# HELLO1.net
KiCad netlist of a schematic drawn in EAGLE
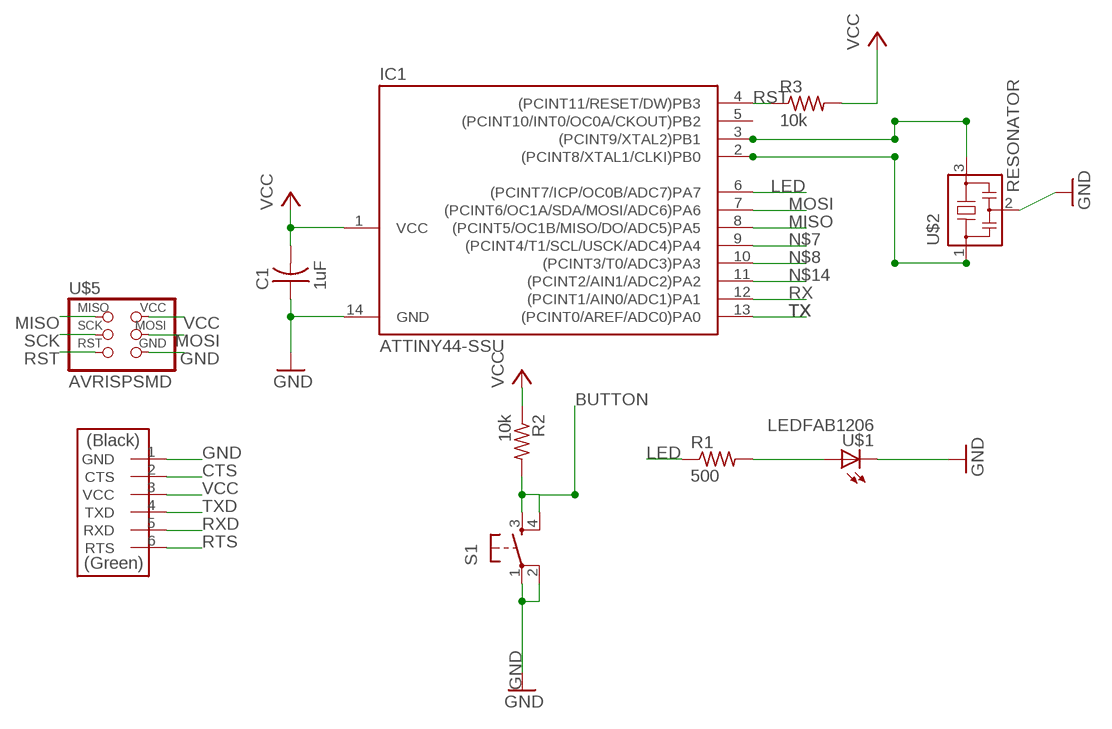
[diagram p0: schematic, sheet 1]

(export (version "E")
  (design (tool "Eeschema 10.0.6"))
  (components
    (comp (ref "C1")
      (value "1uF")
      (footprint "eagle-import:C1206FAB")
      (libsource (lib "eagle-import") (part "CAP-US1206FAB"))
    )
    (comp (ref "IC1")
      (value "ATTINY44-SSU")
      (footprint "eagle-import:SOIC14")
      (libsource (lib "eagle-import") (part "ATTINY44-SSU"))
    )
    (comp (ref "R1")
      (value "500")
      (footprint "eagle-import:R1206FAB")
      (libsource (lib "eagle-import") (part "RES-US1206FAB"))
    )
    (comp (ref "R2")
      (value "10k")
      (footprint "eagle-import:R1206FAB")
      (libsource (lib "eagle-import") (part "RES-US1206FAB"))
    )
    (comp (ref "R3")
      (value "10k")
      (footprint "eagle-import:R1206FAB")
      (libsource (lib "eagle-import") (part "RES-US1206FAB"))
    )
    (comp (ref "S1")
      (value "6MM_SWITCH6MM_SWITCH")
      (footprint "eagle-import:6MM_SWITCH")
      (libsource (lib "eagle-import") (part "6MM_SWITCH6MM_SWITCH"))
    )
    (comp (ref "U$1")
      (value "LEDFAB1206")
      (footprint "eagle-import:LED1206FAB")
      (libsource (lib "eagle-import") (part "LEDFAB1206"))
    )
    (comp (ref "U$2")
      (value "RESONATOR")
      (footprint "eagle-import:EFOBM")
      (libsource (lib "eagle-import") (part "RESONATOR"))
    )
    (comp (ref "U$4")
      (value "FTDI-SMD-HEADER")
      (footprint "eagle-import:1X06SMD")
      (libsource (lib "eagle-import") (part "FTDI-SMD-HEADER"))
    )
    (comp (ref "U$5")
      (value "AVRISPSMD")
      (footprint "eagle-import:2X03SMD")
      (libsource (lib "eagle-import") (part "AVRISPSMD"))
    )
  )
  (nets
    (net (code "1") (name "/BUTTON") (class "Default")
      (node (ref "R2") (pin "2") (pinfunction "2_2") (pintype "passive"))
      (node (ref "S1") (pin "3") (pinfunction "S_3") (pintype "passive"))
      (node (ref "S1") (pin "4") (pinfunction "S1_4") (pintype "passive"))
    )
    (net (code "2") (name "/CTS") (class "Default")
      (node (ref "U$4") (pin "2") (pinfunction "CTS_2") (pintype "bidirectional"))
    )
    (net (code "3") (name "/LED") (class "Default")
      (node (ref "IC1") (pin "6") (pinfunction "(PCINT7/ICP/OC0B/ADC7)PA7_6") (pintype "bidirectional"))
      (node (ref "R1") (pin "1") (pinfunction "1_1") (pintype "passive"))
    )
    (net (code "4") (name "/MISO") (class "Default")
      (node (ref "IC1") (pin "8") (pinfunction "(PCINT5/OC1B/MISO/DO/ADC5)PA5_8") (pintype "bidirectional"))
      (node (ref "U$5") (pin "1") (pinfunction "MISO_1") (pintype "passive"))
    )
    (net (code "5") (name "/MOSI") (class "Default")
      (node (ref "IC1") (pin "7") (pinfunction "(PCINT6/OC1A/SDA/MOSI/ADC6)PA6_7") (pintype "bidirectional"))
      (node (ref "U$5") (pin "4") (pinfunction "MOSI_4") (pintype "passive"))
    )
    (net (code "6") (name "/N$7") (class "Default")
      (node (ref "IC1") (pin "9") (pinfunction "(PCINT4/T1/SCL/USCK/ADC4)PA4_9") (pintype "bidirectional"))
    )
    (net (code "7") (name "/N$8") (class "Default")
      (node (ref "IC1") (pin "10") (pinfunction "(PCINT3/T0/ADC3)PA3_10") (pintype "bidirectional"))
    )
    (net (code "8") (name "/N$14") (class "Default")
      (node (ref "IC1") (pin "11") (pinfunction "(PCINT2/AIN1/ADC2)PA2_11") (pintype "bidirectional"))
    )
    (net (code "9") (name "/RST") (class "Default")
      (node (ref "IC1") (pin "4") (pinfunction "(PCINT11/RESET/DW)PB3_4") (pintype "bidirectional"))
      (node (ref "R3") (pin "1") (pinfunction "1_1") (pintype "passive"))
      (node (ref "U$5") (pin "5") (pinfunction "RST_5") (pintype "passive"))
    )
    (net (code "10") (name "/RTS") (class "Default")
      (node (ref "U$4") (pin "6") (pinfunction "RTS_6") (pintype "bidirectional"))
    )
    (net (code "11") (name "/RX") (class "Default")
      (node (ref "IC1") (pin "12") (pinfunction "(PCINT1/AIN0/ADC1)PA1_12") (pintype "bidirectional"))
    )
    (net (code "12") (name "/RXD") (class "Default")
      (node (ref "U$4") (pin "5") (pinfunction "RXD_5") (pintype "bidirectional"))
    )
    (net (code "13") (name "/SCK") (class "Default")
      (node (ref "U$5") (pin "3") (pinfunction "SCK_3") (pintype "passive"))
    )
    (net (code "14") (name "/TX") (class "Default")
      (node (ref "IC1") (pin "13") (pinfunction "(PCINT0/AREF/ADC0)PA0_13") (pintype "bidirectional"))
    )
    (net (code "15") (name "/TXD") (class "Default")
      (node (ref "U$4") (pin "4") (pinfunction "TXD_4") (pintype "bidirectional"))
    )
    (net (code "16") (name "GND") (class "Default")
      (node (ref "C1") (pin "1") (pinfunction "1_1") (pintype "passive"))
      (node (ref "IC1") (pin "14") (pinfunction "GND_14") (pintype "power_in"))
      (node (ref "S1") (pin "1") (pinfunction "P_1") (pintype "passive"))
      (node (ref "S1") (pin "2") (pinfunction "P1_2") (pintype "passive"))
      (node (ref "U$1") (pin "2") (pinfunction "C_2") (pintype "passive"))
      (node (ref "U$2") (pin "2") (pinfunction "2_2") (pintype "passive"))
      (node (ref "U$4") (pin "1") (pinfunction "GND_1") (pintype "bidirectional"))
      (node (ref "U$5") (pin "6") (pinfunction "GND_6") (pintype "passive"))
    )
    (net (code "17") (name "Net-(IC1-(PCINT8{slash}XTAL1{slash}CLKI)PB0)") (class "Default")
      (node (ref "IC1") (pin "2") (pinfunction "(PCINT8/XTAL1/CLKI)PB0_2") (pintype "bidirectional"))
      (node (ref "U$2") (pin "1") (pinfunction "1_1") (pintype "passive"))
    )
    (net (code "18") (name "Net-(IC1-(PCINT9{slash}XTAL2)PB1)") (class "Default")
      (node (ref "IC1") (pin "3") (pinfunction "(PCINT9/XTAL2)PB1_3") (pintype "bidirectional"))
      (node (ref "U$2") (pin "3") (pinfunction "3_3") (pintype "passive"))
    )
    (net (code "19") (name "Net-(U$1-A)") (class "Default")
      (node (ref "R1") (pin "2") (pinfunction "2_2") (pintype "passive"))
      (node (ref "U$1") (pin "1") (pinfunction "A_1") (pintype "passive"))
    )
    (net (code "20") (name "VCC") (class "Default")
      (node (ref "C1") (pin "2") (pinfunction "2_2") (pintype "passive"))
      (node (ref "IC1") (pin "1") (pinfunction "VCC_1") (pintype "power_in"))
      (node (ref "R2") (pin "1") (pinfunction "1_1") (pintype "passive"))
      (node (ref "R3") (pin "2") (pinfunction "2_2") (pintype "passive"))
      (node (ref "U$4") (pin "3") (pinfunction "VCC_3") (pintype "bidirectional"))
      (node (ref "U$5") (pin "2") (pinfunction "VCC_2") (pintype "passive"))
    )
    (net (code "21") (name "unconnected-(IC1-(PCINT10{slash}INT0{slash}OC0A{slash}CKOUT)PB2-Pad5)") (class "Default")
      (node (ref "IC1") (pin "5") (pinfunction "(PCINT10/INT0/OC0A/CKOUT)PB2_5") (pintype "bidirectional"))
    )
  )
)
